# David_Smith-th.net
KiCad netlist of a schematic drawn in EAGLE
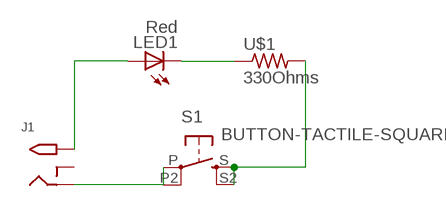
[diagram p0: schematic, sheet 1]

(export (version "E")
  (design (tool "Eeschema 10.0.6"))
  (components
    (comp (ref "J1")
      (value "2.1MMJACKTHM")
      (footprint "eagle-import:PJ-102A")
      (libsource (lib "eagle-import") (part "2.1MMJACKTHM"))
    )
    (comp (ref "LED1")
      (value "Red")
      (footprint "eagle-import:LED5MM")
      (libsource (lib "eagle-import") (part "LED5MM"))
    )
    (comp (ref "S1")
      (value "BUTTON-TACTILE-SQUARE")
      (footprint "eagle-import:BUTTON-TACTILE-SQUARE-ADAFRUIT1010")
      (libsource (lib "eagle-import") (part "BUTTON-TACTILE-SQUARE"))
    )
    (comp (ref "U$1")
      (value "330Ohms")
      (footprint "eagle-import:RESAD1160W55L680D260_HS")
      (libsource (lib "eagle-import") (part "RESISTORTH-1/4W-CARBON"))
    )
  )
  (nets
    (net (code "1") (name "Net-(J1-PadTIP)") (class "Default")
      (node (ref "J1") (pin "TIP") (pinfunction "TIP_TIP") (pintype "bidirectional"))
      (node (ref "LED1") (pin "A") (pinfunction "A_A") (pintype "passive"))
    )
    (net (code "2") (name "Net-(LED1-C)") (class "Default")
      (node (ref "LED1") (pin "K") (pinfunction "C_K") (pintype "passive"))
      (node (ref "U$1") (pin "1") (pinfunction "1_1") (pintype "passive"))
    )
    (net (code "3") (name "Net-(S1-P1)") (class "Default")
      (node (ref "J1") (pin "RING") (pinfunction "RING_RING") (pintype "bidirectional"))
      (node (ref "S1") (pin "P") (pinfunction "P_P") (pintype "passive"))
      (node (ref "S1") (pin "P2") (pinfunction "P1_P2") (pintype "passive"))
    )
    (net (code "4") (name "Net-(S1-S1)") (class "Default")
      (node (ref "S1") (pin "S") (pinfunction "S_S") (pintype "passive"))
      (node (ref "S1") (pin "S2") (pinfunction "S1_S2") (pintype "passive"))
      (node (ref "U$1") (pin "2") (pinfunction "2_2") (pintype "passive"))
    )
    (net (code "5") (name "unconnected-(J1-PadRING_SW)") (class "Default")
      (node (ref "J1") (pin "RING_SW") (pinfunction "RING_SW_RING_SW") (pintype "bidirectional"))
    )
  )
)
